# SoM-HighSpeed.net
KiCad netlist of a schematic drawn in Altium Designer
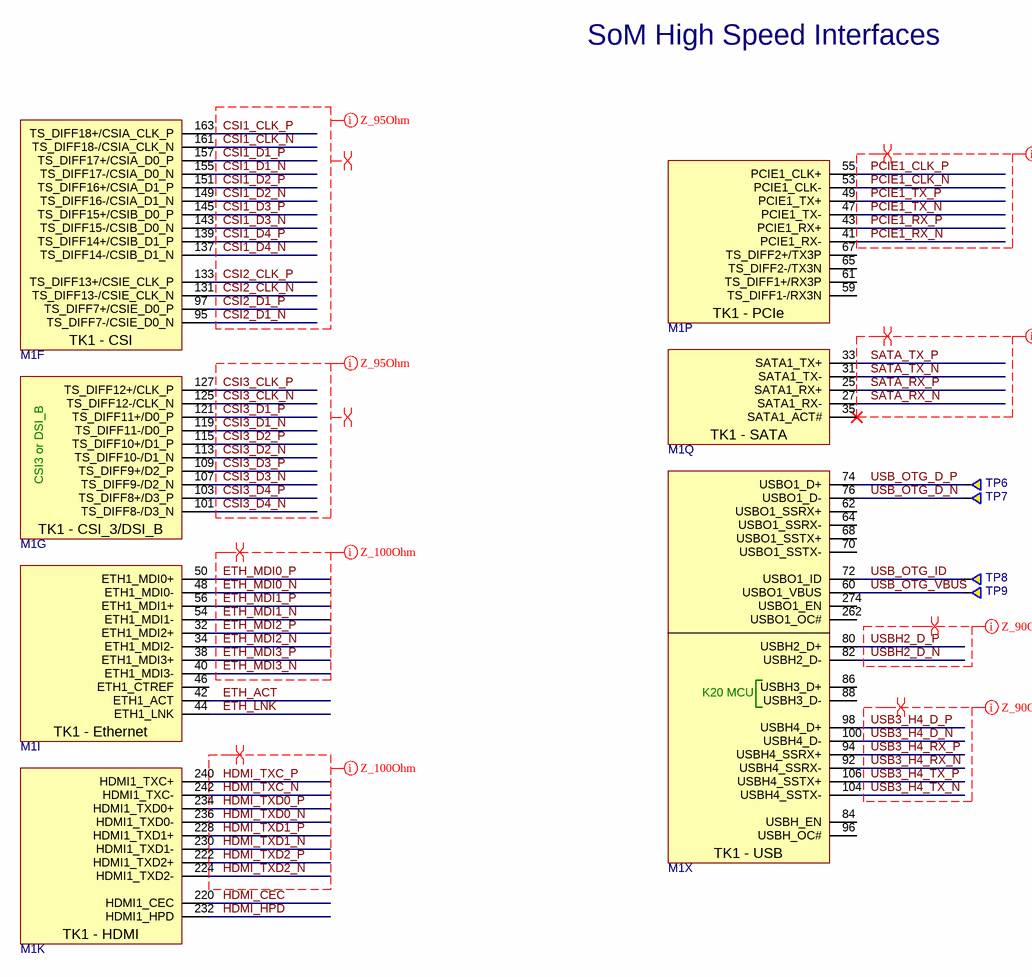
[diagram p0: SoM-HighSpeed.SchDoc]

(export (version "E")
  (design (tool "Eeschema 10.0.6"))
  (components
    (comp (ref "M1")
      (value "MM70-314-310B1")
      (footprint "Apalis-H")
      (description "Toradex Apalis TK1, Horizontal")
      (fields (field (name "PART NUMBER") "Apalis-TK1-H") (field (name "MANUFACTURER") "JAE Electronics"))
      (libsource (lib "TK1Baseboard") (part "Apalis-TK1-H"))
    )
    (comp (ref "TP6")
      (value "TP-R-1.5")
      (footprint "TP-R-1.5")
      (description "Testpad, round, 1.5mm")
      (libsource (lib "TK1Baseboard") (part "TP-R-1.5"))
    )
    (comp (ref "TP7")
      (value "TP-R-1.5")
      (footprint "TP-R-1.5")
      (description "Testpad, round, 1.5mm")
      (libsource (lib "TK1Baseboard") (part "TP-R-1.5"))
    )
    (comp (ref "TP8")
      (value "TP-R-1.5")
      (footprint "TP-R-1.5")
      (description "Testpad, round, 1.5mm")
      (libsource (lib "TK1Baseboard") (part "TP-R-1.5"))
    )
    (comp (ref "TP9")
      (value "TP-R-1.5")
      (footprint "TP-R-1.5")
      (description "Testpad, round, 1.5mm")
      (libsource (lib "TK1Baseboard") (part "TP-R-1.5"))
    )
  )
  (nets
    (net (code "1") (name "/CSI1_CLK_N") (class "Default")
      (node (ref "M1") (pin "161") (pinfunction "TS_DIFF18-/CSIA_CLK_N_161") (pintype "passive"))
    )
    (net (code "2") (name "/CSI1_CLK_P") (class "Default")
      (node (ref "M1") (pin "163") (pinfunction "TS_DIFF18+/CSIA_CLK_P_163") (pintype "passive"))
    )
    (net (code "3") (name "/CSI1_D1_N") (class "Default")
      (node (ref "M1") (pin "155") (pinfunction "TS_DIFF17-/CSIA_D0_N_155") (pintype "passive"))
    )
    (net (code "4") (name "/CSI1_D1_P") (class "Default")
      (node (ref "M1") (pin "157") (pinfunction "TS_DIFF17+/CSIA_D0_P_157") (pintype "passive"))
    )
    (net (code "5") (name "/CSI1_D2_N") (class "Default")
      (node (ref "M1") (pin "149") (pinfunction "TS_DIFF16-/CSIA_D1_N_149") (pintype "passive"))
    )
    (net (code "6") (name "/CSI1_D2_P") (class "Default")
      (node (ref "M1") (pin "151") (pinfunction "TS_DIFF16+/CSIA_D1_P_151") (pintype "passive"))
    )
    (net (code "7") (name "/CSI1_D3_N") (class "Default")
      (node (ref "M1") (pin "143") (pinfunction "TS_DIFF15-/CSIB_D0_N_143") (pintype "passive"))
    )
    (net (code "8") (name "/CSI1_D3_P") (class "Default")
      (node (ref "M1") (pin "145") (pinfunction "TS_DIFF15+/CSIB_D0_P_145") (pintype "passive"))
    )
    (net (code "9") (name "/CSI1_D4_N") (class "Default")
      (node (ref "M1") (pin "137") (pinfunction "TS_DIFF14-/CSIB_D1_N_137") (pintype "passive"))
    )
    (net (code "10") (name "/CSI1_D4_P") (class "Default")
      (node (ref "M1") (pin "139") (pinfunction "TS_DIFF14+/CSIB_D1_P_139") (pintype "passive"))
    )
    (net (code "11") (name "/CSI2_CLK_N") (class "Default")
      (node (ref "M1") (pin "131") (pinfunction "TS_DIFF13-/CSIE_CLK_N_131") (pintype "passive"))
    )
    (net (code "12") (name "/CSI2_CLK_P") (class "Default")
      (node (ref "M1") (pin "133") (pinfunction "TS_DIFF13+/CSIE_CLK_P_133") (pintype "passive"))
    )
    (net (code "13") (name "/CSI2_D1_N") (class "Default")
      (node (ref "M1") (pin "95") (pinfunction "TS_DIFF7-/CSIE_D0_N_95") (pintype "passive"))
    )
    (net (code "14") (name "/CSI2_D1_P") (class "Default")
      (node (ref "M1") (pin "97") (pinfunction "TS_DIFF7+/CSIE_D0_P_97") (pintype "passive"))
    )
    (net (code "15") (name "/CSI3_CLK_N") (class "Default")
      (node (ref "M1") (pin "125") (pinfunction "TS_DIFF12-/CLK_N_125") (pintype "passive"))
    )
    (net (code "16") (name "/CSI3_CLK_P") (class "Default")
      (node (ref "M1") (pin "127") (pinfunction "TS_DIFF12+/CLK_P_127") (pintype "passive"))
    )
    (net (code "17") (name "/CSI3_D1_N") (class "Default")
      (node (ref "M1") (pin "119") (pinfunction "TS_DIFF11-/D0_P_119") (pintype "passive"))
    )
    (net (code "18") (name "/CSI3_D1_P") (class "Default")
      (node (ref "M1") (pin "121") (pinfunction "TS_DIFF11+/D0_P_121") (pintype "passive"))
    )
    (net (code "19") (name "/CSI3_D2_N") (class "Default")
      (node (ref "M1") (pin "113") (pinfunction "TS_DIFF10-/D1_N_113") (pintype "passive"))
    )
    (net (code "20") (name "/CSI3_D2_P") (class "Default")
      (node (ref "M1") (pin "115") (pinfunction "TS_DIFF10+/D1_P_115") (pintype "passive"))
    )
    (net (code "21") (name "/CSI3_D3_N") (class "Default")
      (node (ref "M1") (pin "107") (pinfunction "TS_DIFF9-/D2_N_107") (pintype "passive"))
    )
    (net (code "22") (name "/CSI3_D3_P") (class "Default")
      (node (ref "M1") (pin "109") (pinfunction "TS_DIFF9+/D2_P_109") (pintype "passive"))
    )
    (net (code "23") (name "/CSI3_D4_N") (class "Default")
      (node (ref "M1") (pin "101") (pinfunction "TS_DIFF8-/D3_N_101") (pintype "passive"))
    )
    (net (code "24") (name "/CSI3_D4_P") (class "Default")
      (node (ref "M1") (pin "103") (pinfunction "TS_DIFF8+/D3_P_103") (pintype "passive"))
    )
    (net (code "25") (name "/ETH_ACT") (class "Default")
      (node (ref "M1") (pin "42") (pinfunction "ETH1_ACT_42") (pintype "passive"))
    )
    (net (code "26") (name "/ETH_LNK") (class "Default")
      (node (ref "M1") (pin "44") (pinfunction "ETH1_LNK_44") (pintype "passive"))
    )
    (net (code "27") (name "/ETH_MDI0_N") (class "Default")
      (node (ref "M1") (pin "48") (pinfunction "ETH1_MDI0-_48") (pintype "passive"))
    )
    (net (code "28") (name "/ETH_MDI0_P") (class "Default")
      (node (ref "M1") (pin "50") (pinfunction "ETH1_MDI0+_50") (pintype "passive"))
    )
    (net (code "29") (name "/ETH_MDI1_N") (class "Default")
      (node (ref "M1") (pin "54") (pinfunction "ETH1_MDI1-_54") (pintype "passive"))
    )
    (net (code "30") (name "/ETH_MDI1_P") (class "Default")
      (node (ref "M1") (pin "56") (pinfunction "ETH1_MDI1+_56") (pintype "passive"))
    )
    (net (code "31") (name "/ETH_MDI2_N") (class "Default")
      (node (ref "M1") (pin "34") (pinfunction "ETH1_MDI2-_34") (pintype "passive"))
    )
    (net (code "32") (name "/ETH_MDI2_P") (class "Default")
      (node (ref "M1") (pin "32") (pinfunction "ETH1_MDI2+_32") (pintype "passive"))
    )
    (net (code "33") (name "/ETH_MDI3_N") (class "Default")
      (node (ref "M1") (pin "40") (pinfunction "ETH1_MDI3-_40") (pintype "passive"))
    )
    (net (code "34") (name "/ETH_MDI3_P") (class "Default")
      (node (ref "M1") (pin "38") (pinfunction "ETH1_MDI3+_38") (pintype "passive"))
    )
    (net (code "35") (name "/HDMI_CEC") (class "Default")
      (node (ref "M1") (pin "220") (pinfunction "HDMI1_CEC_220") (pintype "passive"))
    )
    (net (code "36") (name "/HDMI_HPD") (class "Default")
      (node (ref "M1") (pin "232") (pinfunction "HDMI1_HPD_232") (pintype "passive"))
    )
    (net (code "37") (name "/HDMI_TXC_N") (class "Default")
      (node (ref "M1") (pin "242") (pinfunction "HDMI1_TXC-_242") (pintype "passive"))
    )
    (net (code "38") (name "/HDMI_TXC_P") (class "Default")
      (node (ref "M1") (pin "240") (pinfunction "HDMI1_TXC+_240") (pintype "passive"))
    )
    (net (code "39") (name "/HDMI_TXD0_N") (class "Default")
      (node (ref "M1") (pin "236") (pinfunction "HDMI1_TXD0-_236") (pintype "passive"))
    )
    (net (code "40") (name "/HDMI_TXD0_P") (class "Default")
      (node (ref "M1") (pin "234") (pinfunction "HDMI1_TXD0+_234") (pintype "passive"))
    )
    (net (code "41") (name "/HDMI_TXD1_N") (class "Default")
      (node (ref "M1") (pin "230") (pinfunction "HDMI1_TXD1-_230") (pintype "passive"))
    )
    (net (code "42") (name "/HDMI_TXD1_P") (class "Default")
      (node (ref "M1") (pin "228") (pinfunction "HDMI1_TXD1+_228") (pintype "passive"))
    )
    (net (code "43") (name "/HDMI_TXD2_N") (class "Default")
      (node (ref "M1") (pin "224") (pinfunction "HDMI1_TXD2-_224") (pintype "passive"))
    )
    (net (code "44") (name "/HDMI_TXD2_P") (class "Default")
      (node (ref "M1") (pin "222") (pinfunction "HDMI1_TXD2+_222") (pintype "passive"))
    )
    (net (code "45") (name "/PCIE1_CLK_N") (class "Default")
      (node (ref "M1") (pin "53") (pinfunction "PCIE1_CLK-_53") (pintype "passive"))
    )
    (net (code "46") (name "/PCIE1_CLK_P") (class "Default")
      (node (ref "M1") (pin "55") (pinfunction "PCIE1_CLK+_55") (pintype "passive"))
    )
    (net (code "47") (name "/PCIE1_RX_N") (class "Default")
      (node (ref "M1") (pin "41") (pinfunction "PCIE1_RX-_41") (pintype "passive"))
    )
    (net (code "48") (name "/PCIE1_RX_P") (class "Default")
      (node (ref "M1") (pin "43") (pinfunction "PCIE1_RX+_43") (pintype "passive"))
    )
    (net (code "49") (name "/PCIE1_TX_N") (class "Default")
      (node (ref "M1") (pin "47") (pinfunction "PCIE1_TX-_47") (pintype "passive"))
    )
    (net (code "50") (name "/PCIE1_TX_P") (class "Default")
      (node (ref "M1") (pin "49") (pinfunction "PCIE1_TX+_49") (pintype "passive"))
    )
    (net (code "51") (name "/SATA_RX_N") (class "Default")
      (node (ref "M1") (pin "27") (pinfunction "SATA1_RX-_27") (pintype "passive"))
    )
    (net (code "52") (name "/SATA_RX_P") (class "Default")
      (node (ref "M1") (pin "25") (pinfunction "SATA1_RX+_25") (pintype "passive"))
    )
    (net (code "53") (name "/SATA_TX_N") (class "Default")
      (node (ref "M1") (pin "31") (pinfunction "SATA1_TX-_31") (pintype "passive"))
    )
    (net (code "54") (name "/SATA_TX_P") (class "Default")
      (node (ref "M1") (pin "33") (pinfunction "SATA1_TX+_33") (pintype "passive"))
    )
    (net (code "55") (name "/USB3_H4_D_N") (class "Default")
      (node (ref "M1") (pin "100") (pinfunction "USBH4_D-_100") (pintype "passive"))
    )
    (net (code "56") (name "/USB3_H4_D_P") (class "Default")
      (node (ref "M1") (pin "98") (pinfunction "USBH4_D+_98") (pintype "passive"))
    )
    (net (code "57") (name "/USB3_H4_RX_N") (class "Default")
      (node (ref "M1") (pin "92") (pinfunction "USBH4_SSRX-_92") (pintype "passive"))
    )
    (net (code "58") (name "/USB3_H4_RX_P") (class "Default")
      (node (ref "M1") (pin "94") (pinfunction "USBH4_SSRX+_94") (pintype "passive"))
    )
    (net (code "59") (name "/USB3_H4_TX_N") (class "Default")
      (node (ref "M1") (pin "104") (pinfunction "USBH4_SSTX-_104") (pintype "passive"))
    )
    (net (code "60") (name "/USB3_H4_TX_P") (class "Default")
      (node (ref "M1") (pin "106") (pinfunction "USBH4_SSTX+_106") (pintype "passive"))
    )
    (net (code "61") (name "/USBH2_D_N") (class "Default")
      (node (ref "M1") (pin "82") (pinfunction "USBH2_D-_82") (pintype "passive"))
    )
    (net (code "62") (name "/USBH2_D_P") (class "Default")
      (node (ref "M1") (pin "80") (pinfunction "USBH2_D+_80") (pintype "passive"))
    )
    (net (code "63") (name "/USB_OTG_D_N") (class "Default")
      (node (ref "M1") (pin "76") (pinfunction "USBO1_D-_76") (pintype "passive"))
      (node (ref "TP7") (pin "1") (pintype "passive"))
    )
    (net (code "64") (name "/USB_OTG_D_P") (class "Default")
      (node (ref "M1") (pin "74") (pinfunction "USBO1_D+_74") (pintype "passive"))
      (node (ref "TP6") (pin "1") (pintype "passive"))
    )
    (net (code "65") (name "/USB_OTG_ID") (class "Default")
      (node (ref "M1") (pin "72") (pinfunction "USBO1_ID_72") (pintype "passive"))
      (node (ref "TP8") (pin "1") (pintype "passive"))
    )
    (net (code "66") (name "/USB_OTG_VBUS") (class "Default")
      (node (ref "M1") (pin "60") (pinfunction "USBO1_VBUS_60") (pintype "passive"))
      (node (ref "TP9") (pin "1") (pintype "passive"))
    )
    (net (code "67") (name "unconnected-(M1I-ETH1_CTREF-Pad46)") (class "Default")
      (node (ref "M1") (pin "46") (pinfunction "ETH1_CTREF_46") (pintype "passive"))
    )
    (net (code "68") (name "unconnected-(M1P-TS_DIFF1+{slash}RX3P-Pad61)") (class "Default")
      (node (ref "M1") (pin "61") (pinfunction "TS_DIFF1+/RX3P_61") (pintype "passive"))
    )
    (net (code "69") (name "unconnected-(M1P-TS_DIFF1-{slash}RX3N-Pad59)") (class "Default")
      (node (ref "M1") (pin "59") (pinfunction "TS_DIFF1-/RX3N_59") (pintype "passive"))
    )
    (net (code "70") (name "unconnected-(M1P-TS_DIFF2+{slash}TX3P-Pad67)") (class "Default")
      (node (ref "M1") (pin "67") (pinfunction "TS_DIFF2+/TX3P_67") (pintype "passive"))
    )
    (net (code "71") (name "unconnected-(M1P-TS_DIFF2-{slash}TX3N-Pad65)") (class "Default")
      (node (ref "M1") (pin "65") (pinfunction "TS_DIFF2-/TX3N_65") (pintype "passive"))
    )
    (net (code "72") (name "unconnected-(M1Q-SATA1_ACT#-Pad35)") (class "Default")
      (node (ref "M1") (pin "35") (pinfunction "SATA1_ACT#_35") (pintype "passive+no_connect"))
    )
    (net (code "73") (name "unconnected-(M1X-USBH3_D+-Pad86)") (class "Default")
      (node (ref "M1") (pin "86") (pinfunction "USBH3_D+_86") (pintype "passive"))
    )
    (net (code "74") (name "unconnected-(M1X-USBH3_D--Pad88)") (class "Default")
      (node (ref "M1") (pin "88") (pinfunction "USBH3_D-_88") (pintype "passive"))
    )
    (net (code "75") (name "unconnected-(M1X-USBH_EN-Pad84)") (class "Default")
      (node (ref "M1") (pin "84") (pinfunction "USBH_EN_84") (pintype "passive"))
    )
    (net (code "76") (name "unconnected-(M1X-USBH_OC#-Pad96)") (class "Default")
      (node (ref "M1") (pin "96") (pinfunction "USBH_OC#_96") (pintype "passive"))
    )
    (net (code "77") (name "unconnected-(M1X-USBO1_EN-Pad274)") (class "Default")
      (node (ref "M1") (pin "274") (pinfunction "USBO1_EN_274") (pintype "passive"))
    )
    (net (code "78") (name "unconnected-(M1X-USBO1_OC#-Pad262)") (class "Default")
      (node (ref "M1") (pin "262") (pinfunction "USBO1_OC#_262") (pintype "passive"))
    )
    (net (code "79") (name "unconnected-(M1X-USBO1_SSRX+-Pad62)") (class "Default")
      (node (ref "M1") (pin "62") (pinfunction "USBO1_SSRX+_62") (pintype "passive"))
    )
    (net (code "80") (name "unconnected-(M1X-USBO1_SSRX--Pad64)") (class "Default")
      (node (ref "M1") (pin "64") (pinfunction "USBO1_SSRX-_64") (pintype "passive"))
    )
    (net (code "81") (name "unconnected-(M1X-USBO1_SSTX+-Pad68)") (class "Default")
      (node (ref "M1") (pin "68") (pinfunction "USBO1_SSTX+_68") (pintype "passive"))
    )
    (net (code "82") (name "unconnected-(M1X-USBO1_SSTX--Pad70)") (class "Default")
      (node (ref "M1") (pin "70") (pinfunction "USBO1_SSTX-_70") (pintype "passive"))
    )
  )
)
